# usb64.net
KiCad netlist of a schematic drawn in EAGLE
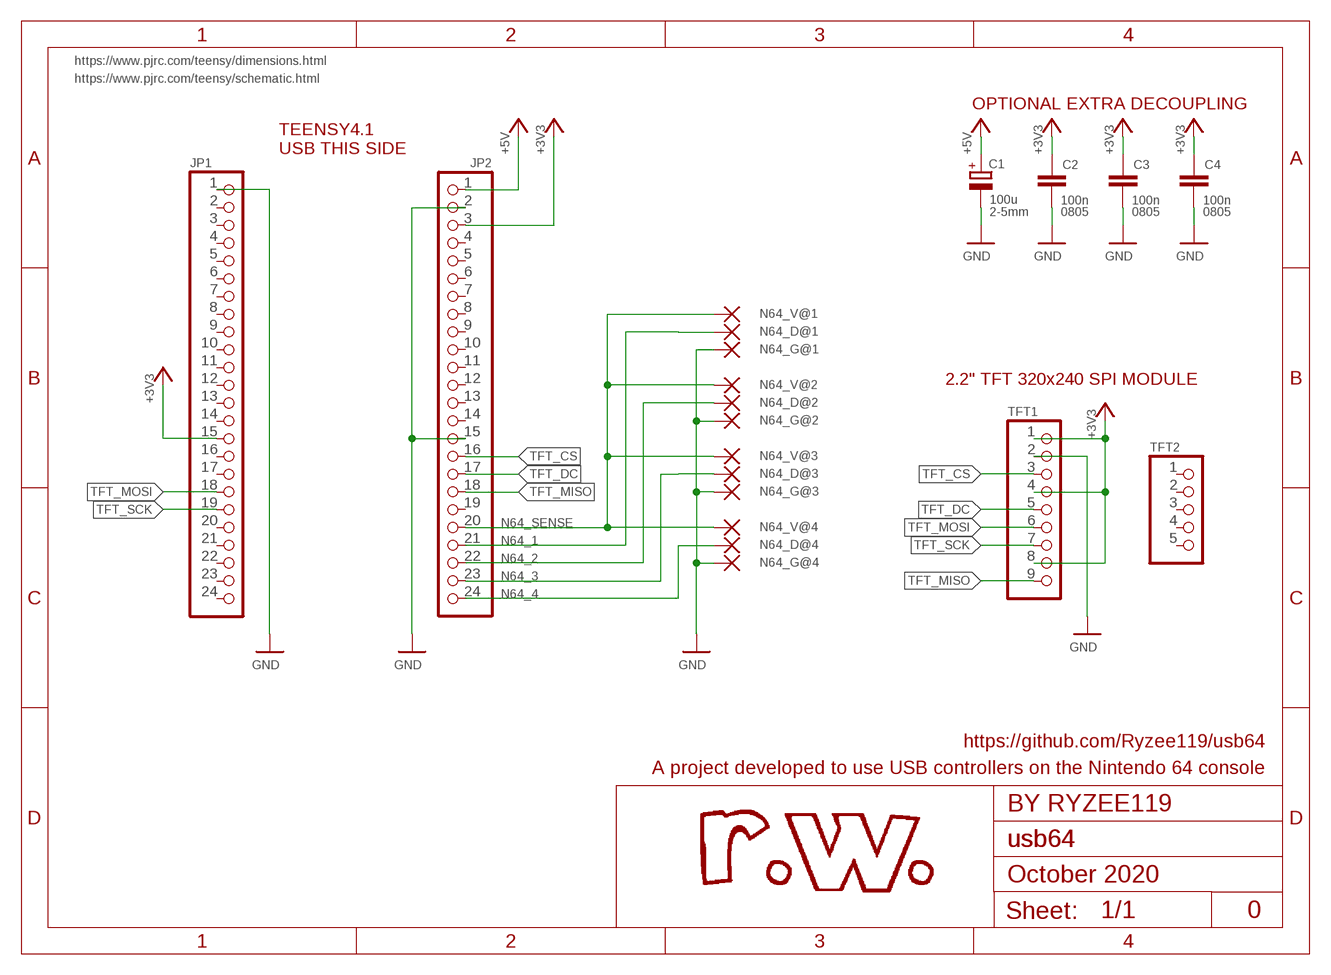
[diagram p0: schematic, sheet 1]

(export (version "E")
  (design (tool "Eeschema 10.0.6"))
  (components
    (comp (ref "C1")
      (value "100u")
      (footprint "eagle-import:E2-5")
      (libsource (lib "eagle-import") (part "CPOL-EUE2-5"))
    )
    (comp (ref "C2")
      (value "100n")
      (footprint "eagle-import:C0805K")
      (libsource (lib "eagle-import") (part "C-EUC0805K"))
    )
    (comp (ref "C3")
      (value "100n")
      (footprint "eagle-import:C0805K")
      (libsource (lib "eagle-import") (part "C-EUC0805K"))
    )
    (comp (ref "C4")
      (value "100n")
      (footprint "eagle-import:C0805K")
      (libsource (lib "eagle-import") (part "C-EUC0805K"))
    )
    (comp (ref "JP1")
      (value "PINHD-1X24")
      (footprint "eagle-import:1X24")
      (libsource (lib "eagle-import") (part "PINHD-1X24"))
    )
    (comp (ref "JP2")
      (value "PINHD-1X24")
      (footprint "eagle-import:1X24")
      (libsource (lib "eagle-import") (part "PINHD-1X24"))
    )
    (comp (ref "N64_D@1")
      (value "SMD2")
      (footprint "eagle-import:SMD1,27-2,54")
      (libsource (lib "eagle-import") (part "SMD2"))
    )
    (comp (ref "N64_D@2")
      (value "SMD2")
      (footprint "eagle-import:SMD1,27-2,54")
      (libsource (lib "eagle-import") (part "SMD2"))
    )
    (comp (ref "N64_D@3")
      (value "SMD2")
      (footprint "eagle-import:SMD1,27-2,54")
      (libsource (lib "eagle-import") (part "SMD2"))
    )
    (comp (ref "N64_D@4")
      (value "SMD2")
      (footprint "eagle-import:SMD1,27-2,54")
      (libsource (lib "eagle-import") (part "SMD2"))
    )
    (comp (ref "N64_G@1")
      (value "SMD2")
      (footprint "eagle-import:SMD1,27-2,54")
      (libsource (lib "eagle-import") (part "SMD2"))
    )
    (comp (ref "N64_G@2")
      (value "SMD2")
      (footprint "eagle-import:SMD1,27-2,54")
      (libsource (lib "eagle-import") (part "SMD2"))
    )
    (comp (ref "N64_G@3")
      (value "SMD2")
      (footprint "eagle-import:SMD1,27-2,54")
      (libsource (lib "eagle-import") (part "SMD2"))
    )
    (comp (ref "N64_G@4")
      (value "SMD2")
      (footprint "eagle-import:SMD1,27-2,54")
      (libsource (lib "eagle-import") (part "SMD2"))
    )
    (comp (ref "N64_V@1")
      (value "SMD2")
      (footprint "eagle-import:SMD1,27-2,54")
      (libsource (lib "eagle-import") (part "SMD2"))
    )
    (comp (ref "N64_V@2")
      (value "SMD2")
      (footprint "eagle-import:SMD1,27-2,54")
      (libsource (lib "eagle-import") (part "SMD2"))
    )
    (comp (ref "N64_V@3")
      (value "SMD2")
      (footprint "eagle-import:SMD1,27-2,54")
      (libsource (lib "eagle-import") (part "SMD2"))
    )
    (comp (ref "N64_V@4")
      (value "SMD2")
      (footprint "eagle-import:SMD1,27-2,54")
      (libsource (lib "eagle-import") (part "SMD2"))
    )
    (comp (ref "TFT1")
      (value "PINHD-1X9")
      (footprint "eagle-import:1X09")
      (libsource (lib "eagle-import") (part "PINHD-1X9"))
    )
    (comp (ref "TFT2")
      (value "PINHD-1X5")
      (footprint "eagle-import:1X05")
      (libsource (lib "eagle-import") (part "PINHD-1X5"))
    )
  )
  (nets
    (net (code "1") (name "+3V3") (class "Default")
      (node (ref "C2") (pin "1") (pinfunction "1_1") (pintype "passive"))
      (node (ref "C3") (pin "1") (pinfunction "1_1") (pintype "passive"))
      (node (ref "C4") (pin "1") (pinfunction "1_1") (pintype "passive"))
      (node (ref "JP1") (pin "15") (pinfunction "15_15") (pintype "passive"))
      (node (ref "JP2") (pin "3") (pinfunction "3_3") (pintype "passive"))
      (node (ref "TFT1") (pin "1") (pinfunction "1_1") (pintype "passive"))
      (node (ref "TFT1") (pin "4") (pinfunction "4_4") (pintype "passive"))
      (node (ref "TFT1") (pin "8") (pinfunction "8_8") (pintype "passive"))
    )
    (net (code "2") (name "+5V") (class "Default")
      (node (ref "C1") (pin "+") (pinfunction "+_+") (pintype "passive"))
      (node (ref "JP2") (pin "1") (pinfunction "1_1") (pintype "passive"))
    )
    (net (code "3") (name "/N64_1") (class "Default")
      (node (ref "JP2") (pin "21") (pinfunction "21_21") (pintype "passive"))
      (node (ref "N64_D@1") (pin "1") (pinfunction "P_1") (pintype "passive"))
    )
    (net (code "4") (name "/N64_2") (class "Default")
      (node (ref "JP2") (pin "22") (pinfunction "22_22") (pintype "passive"))
      (node (ref "N64_D@2") (pin "1") (pinfunction "P_1") (pintype "passive"))
    )
    (net (code "5") (name "/N64_3") (class "Default")
      (node (ref "JP2") (pin "23") (pinfunction "23_23") (pintype "passive"))
      (node (ref "N64_D@3") (pin "1") (pinfunction "P_1") (pintype "passive"))
    )
    (net (code "6") (name "/N64_4") (class "Default")
      (node (ref "JP2") (pin "24") (pinfunction "24_24") (pintype "passive"))
      (node (ref "N64_D@4") (pin "1") (pinfunction "P_1") (pintype "passive"))
    )
    (net (code "7") (name "/N64_SENSE") (class "Default")
      (node (ref "JP2") (pin "20") (pinfunction "20_20") (pintype "passive"))
      (node (ref "N64_V@1") (pin "1") (pinfunction "P_1") (pintype "passive"))
      (node (ref "N64_V@2") (pin "1") (pinfunction "P_1") (pintype "passive"))
      (node (ref "N64_V@3") (pin "1") (pinfunction "P_1") (pintype "passive"))
      (node (ref "N64_V@4") (pin "1") (pinfunction "P_1") (pintype "passive"))
    )
    (net (code "8") (name "GND") (class "Default")
      (node (ref "C1") (pin "-") (pinfunction "-_-") (pintype "passive"))
      (node (ref "C2") (pin "2") (pinfunction "2_2") (pintype "passive"))
      (node (ref "C3") (pin "2") (pinfunction "2_2") (pintype "passive"))
      (node (ref "C4") (pin "2") (pinfunction "2_2") (pintype "passive"))
      (node (ref "JP1") (pin "1") (pinfunction "1_1") (pintype "passive"))
      (node (ref "JP2") (pin "15") (pinfunction "15_15") (pintype "passive"))
      (node (ref "JP2") (pin "2") (pinfunction "2_2") (pintype "passive"))
      (node (ref "N64_G@1") (pin "1") (pinfunction "P_1") (pintype "passive"))
      (node (ref "N64_G@2") (pin "1") (pinfunction "P_1") (pintype "passive"))
      (node (ref "N64_G@3") (pin "1") (pinfunction "P_1") (pintype "passive"))
      (node (ref "N64_G@4") (pin "1") (pinfunction "P_1") (pintype "passive"))
      (node (ref "TFT1") (pin "2") (pinfunction "2_2") (pintype "passive"))
    )
    (net (code "9") (name "TFT_CS") (class "Default")
      (node (ref "JP2") (pin "16") (pinfunction "16_16") (pintype "passive"))
      (node (ref "TFT1") (pin "3") (pinfunction "3_3") (pintype "passive"))
    )
    (net (code "10") (name "TFT_DC") (class "Default")
      (node (ref "JP2") (pin "17") (pinfunction "17_17") (pintype "passive"))
      (node (ref "TFT1") (pin "5") (pinfunction "5_5") (pintype "passive"))
    )
    (net (code "11") (name "TFT_MISO") (class "Default")
      (node (ref "JP2") (pin "18") (pinfunction "18_18") (pintype "passive"))
      (node (ref "TFT1") (pin "9") (pinfunction "9_9") (pintype "passive"))
    )
    (net (code "12") (name "TFT_MOSI") (class "Default")
      (node (ref "JP1") (pin "18") (pinfunction "18_18") (pintype "passive"))
      (node (ref "TFT1") (pin "6") (pinfunction "6_6") (pintype "passive"))
    )
    (net (code "13") (name "TFT_SCK") (class "Default")
      (node (ref "JP1") (pin "19") (pinfunction "19_19") (pintype "passive"))
      (node (ref "TFT1") (pin "7") (pinfunction "7_7") (pintype "passive"))
    )
    (net (code "14") (name "unconnected-(JP1-Pad2)") (class "Default")
      (node (ref "JP1") (pin "2") (pinfunction "2_2") (pintype "passive"))
    )
    (net (code "15") (name "unconnected-(JP1-Pad3)") (class "Default")
      (node (ref "JP1") (pin "3") (pinfunction "3_3") (pintype "passive"))
    )
    (net (code "16") (name "unconnected-(JP1-Pad4)") (class "Default")
      (node (ref "JP1") (pin "4") (pinfunction "4_4") (pintype "passive"))
    )
    (net (code "17") (name "unconnected-(JP1-Pad5)") (class "Default")
      (node (ref "JP1") (pin "5") (pinfunction "5_5") (pintype "passive"))
    )
    (net (code "18") (name "unconnected-(JP1-Pad6)") (class "Default")
      (node (ref "JP1") (pin "6") (pinfunction "6_6") (pintype "passive"))
    )
    (net (code "19") (name "unconnected-(JP1-Pad7)") (class "Default")
      (node (ref "JP1") (pin "7") (pinfunction "7_7") (pintype "passive"))
    )
    (net (code "20") (name "unconnected-(JP1-Pad8)") (class "Default")
      (node (ref "JP1") (pin "8") (pinfunction "8_8") (pintype "passive"))
    )
    (net (code "21") (name "unconnected-(JP1-Pad9)") (class "Default")
      (node (ref "JP1") (pin "9") (pinfunction "9_9") (pintype "passive"))
    )
    (net (code "22") (name "unconnected-(JP1-Pad10)") (class "Default")
      (node (ref "JP1") (pin "10") (pinfunction "10_10") (pintype "passive"))
    )
    (net (code "23") (name "unconnected-(JP1-Pad11)") (class "Default")
      (node (ref "JP1") (pin "11") (pinfunction "11_11") (pintype "passive"))
    )
    (net (code "24") (name "unconnected-(JP1-Pad12)") (class "Default")
      (node (ref "JP1") (pin "12") (pinfunction "12_12") (pintype "passive"))
    )
    (net (code "25") (name "unconnected-(JP1-Pad13)") (class "Default")
      (node (ref "JP1") (pin "13") (pinfunction "13_13") (pintype "passive"))
    )
    (net (code "26") (name "unconnected-(JP1-Pad14)") (class "Default")
      (node (ref "JP1") (pin "14") (pinfunction "14_14") (pintype "passive"))
    )
    (net (code "27") (name "unconnected-(JP1-Pad16)") (class "Default")
      (node (ref "JP1") (pin "16") (pinfunction "16_16") (pintype "passive"))
    )
    (net (code "28") (name "unconnected-(JP1-Pad17)") (class "Default")
      (node (ref "JP1") (pin "17") (pinfunction "17_17") (pintype "passive"))
    )
    (net (code "29") (name "unconnected-(JP1-Pad20)") (class "Default")
      (node (ref "JP1") (pin "20") (pinfunction "20_20") (pintype "passive"))
    )
    (net (code "30") (name "unconnected-(JP1-Pad21)") (class "Default")
      (node (ref "JP1") (pin "21") (pinfunction "21_21") (pintype "passive"))
    )
    (net (code "31") (name "unconnected-(JP1-Pad22)") (class "Default")
      (node (ref "JP1") (pin "22") (pinfunction "22_22") (pintype "passive"))
    )
    (net (code "32") (name "unconnected-(JP1-Pad23)") (class "Default")
      (node (ref "JP1") (pin "23") (pinfunction "23_23") (pintype "passive"))
    )
    (net (code "33") (name "unconnected-(JP1-Pad24)") (class "Default")
      (node (ref "JP1") (pin "24") (pinfunction "24_24") (pintype "passive"))
    )
    (net (code "34") (name "unconnected-(JP2-Pad4)") (class "Default")
      (node (ref "JP2") (pin "4") (pinfunction "4_4") (pintype "passive"))
    )
    (net (code "35") (name "unconnected-(JP2-Pad5)") (class "Default")
      (node (ref "JP2") (pin "5") (pinfunction "5_5") (pintype "passive"))
    )
    (net (code "36") (name "unconnected-(JP2-Pad6)") (class "Default")
      (node (ref "JP2") (pin "6") (pinfunction "6_6") (pintype "passive"))
    )
    (net (code "37") (name "unconnected-(JP2-Pad7)") (class "Default")
      (node (ref "JP2") (pin "7") (pinfunction "7_7") (pintype "passive"))
    )
    (net (code "38") (name "unconnected-(JP2-Pad8)") (class "Default")
      (node (ref "JP2") (pin "8") (pinfunction "8_8") (pintype "passive"))
    )
    (net (code "39") (name "unconnected-(JP2-Pad9)") (class "Default")
      (node (ref "JP2") (pin "9") (pinfunction "9_9") (pintype "passive"))
    )
    (net (code "40") (name "unconnected-(JP2-Pad10)") (class "Default")
      (node (ref "JP2") (pin "10") (pinfunction "10_10") (pintype "passive"))
    )
    (net (code "41") (name "unconnected-(JP2-Pad11)") (class "Default")
      (node (ref "JP2") (pin "11") (pinfunction "11_11") (pintype "passive"))
    )
    (net (code "42") (name "unconnected-(JP2-Pad12)") (class "Default")
      (node (ref "JP2") (pin "12") (pinfunction "12_12") (pintype "passive"))
    )
    (net (code "43") (name "unconnected-(JP2-Pad13)") (class "Default")
      (node (ref "JP2") (pin "13") (pinfunction "13_13") (pintype "passive"))
    )
    (net (code "44") (name "unconnected-(JP2-Pad14)") (class "Default")
      (node (ref "JP2") (pin "14") (pinfunction "14_14") (pintype "passive"))
    )
    (net (code "45") (name "unconnected-(JP2-Pad19)") (class "Default")
      (node (ref "JP2") (pin "19") (pinfunction "19_19") (pintype "passive"))
    )
    (net (code "46") (name "unconnected-(TFT2-Pad1)") (class "Default")
      (node (ref "TFT2") (pin "1") (pinfunction "1_1") (pintype "passive"))
    )
    (net (code "47") (name "unconnected-(TFT2-Pad2)") (class "Default")
      (node (ref "TFT2") (pin "2") (pinfunction "2_2") (pintype "passive"))
    )
    (net (code "48") (name "unconnected-(TFT2-Pad3)") (class "Default")
      (node (ref "TFT2") (pin "3") (pinfunction "3_3") (pintype "passive"))
    )
    (net (code "49") (name "unconnected-(TFT2-Pad4)") (class "Default")
      (node (ref "TFT2") (pin "4") (pinfunction "4_4") (pintype "passive"))
    )
    (net (code "50") (name "unconnected-(TFT2-Pad5)") (class "Default")
      (node (ref "TFT2") (pin "5") (pinfunction "5_5") (pintype "passive"))
    )
  )
)
